# Power.net
KiCad netlist of a schematic drawn in Altium Designer
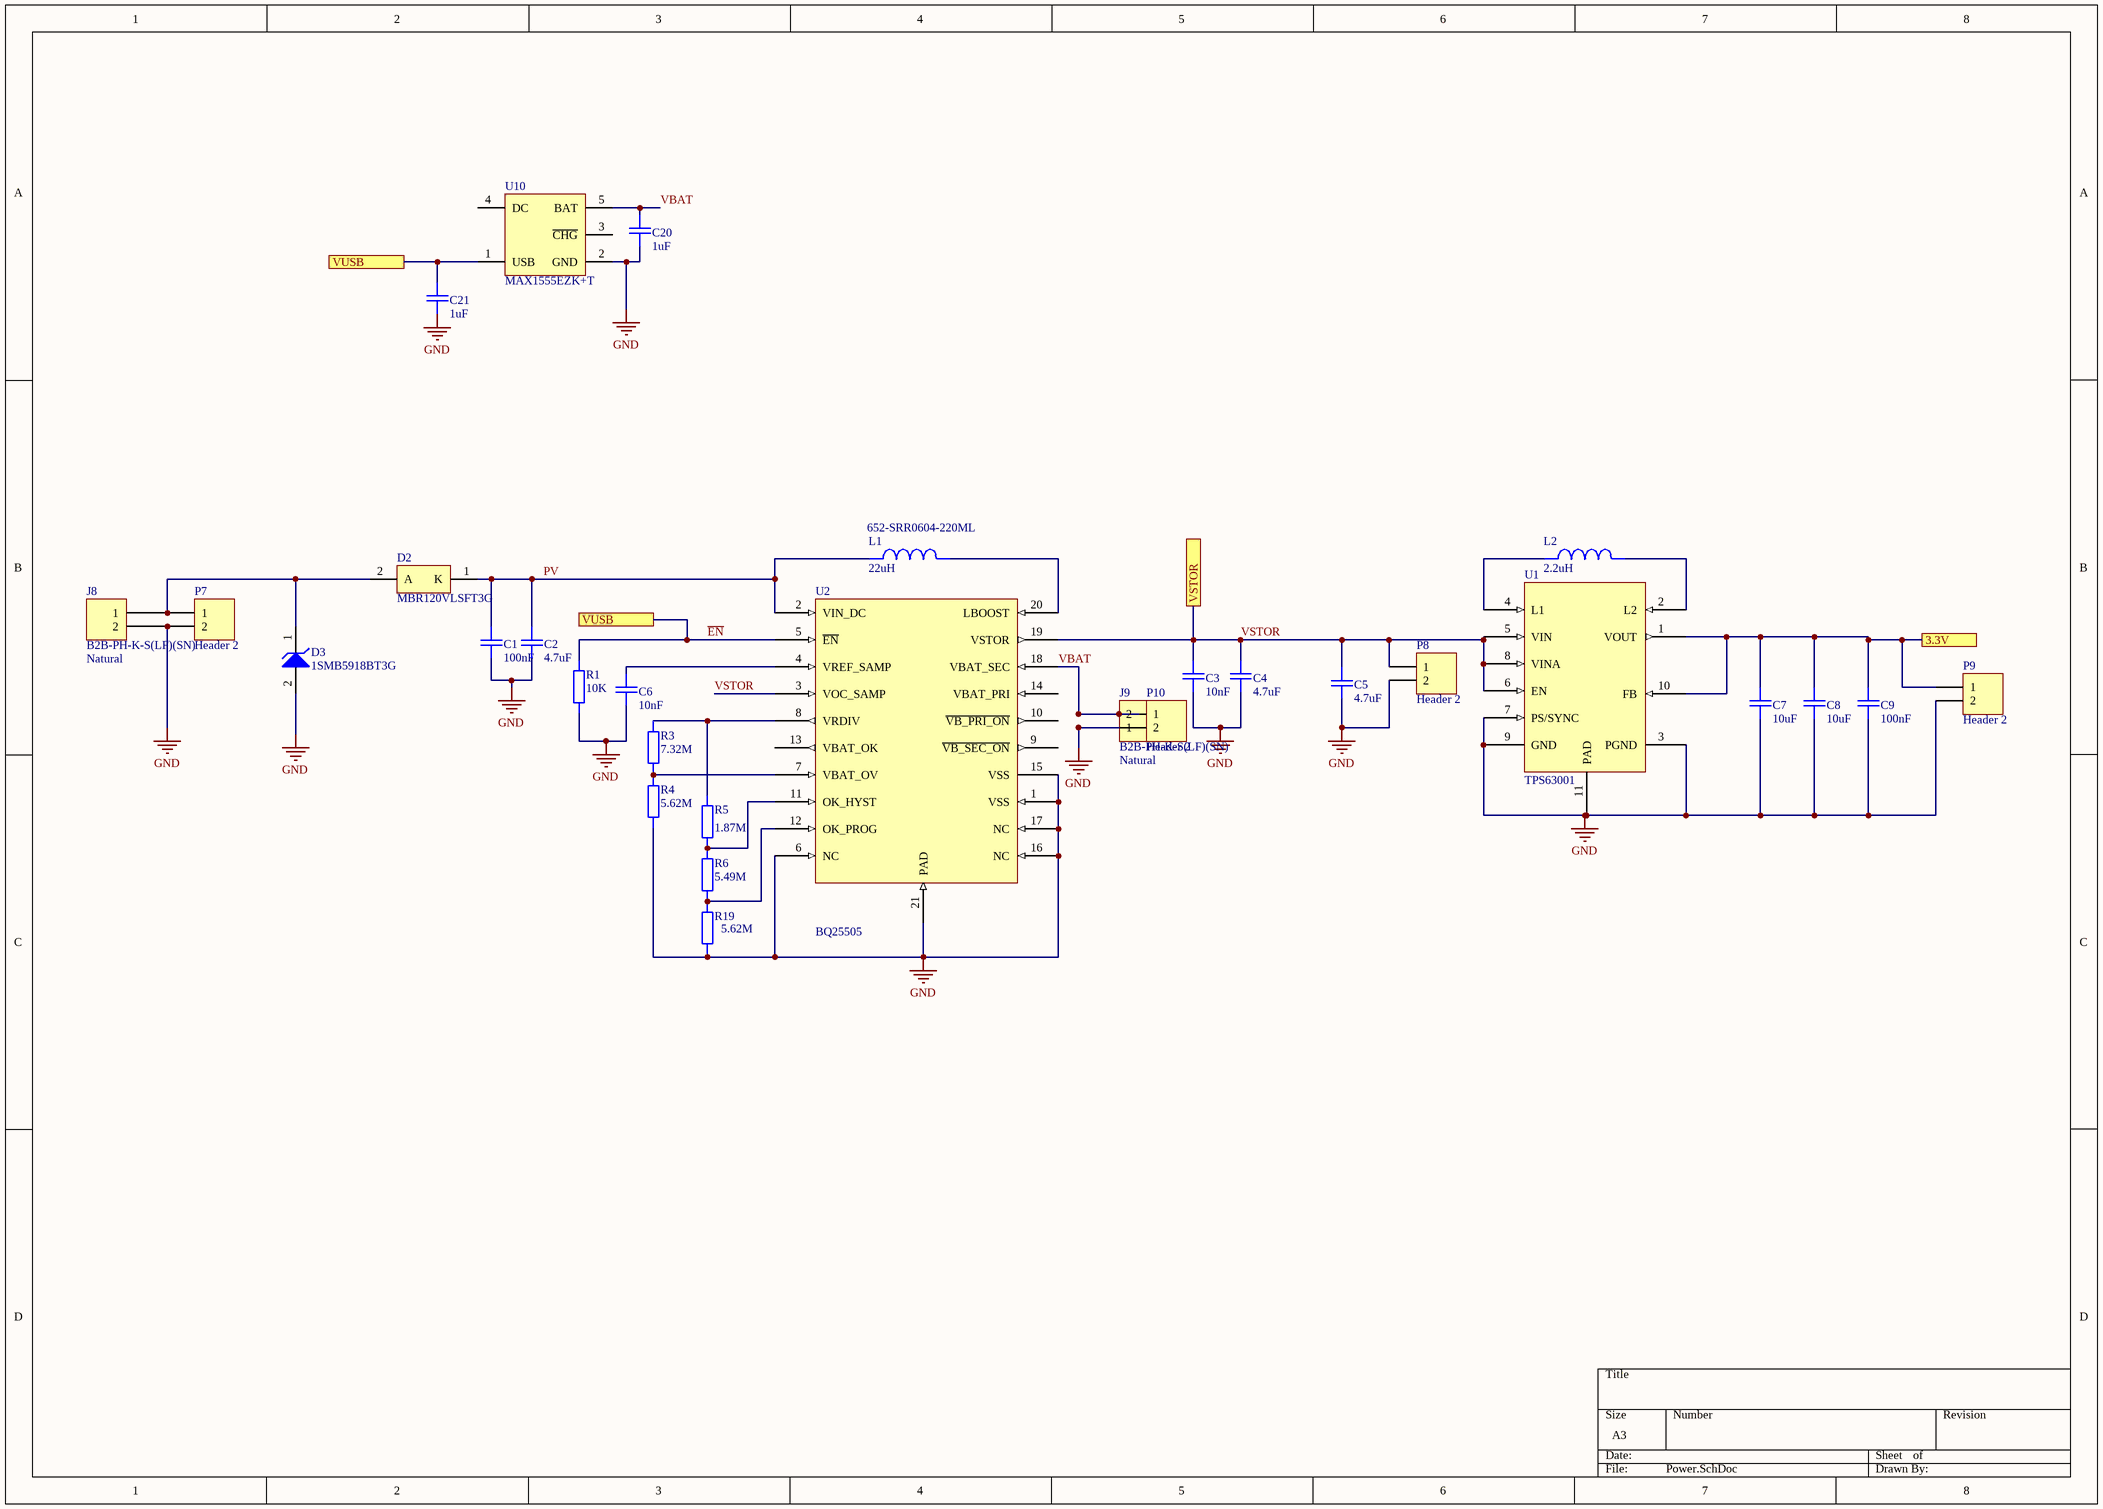
[diagram p0: Power.SchDoc]

(export (version "E")
  (design (tool "Eeschema 10.0.6"))
  (components
    (comp (ref "C1")
      (value "100nF")
      (footprint "C0805")
      (fields
        (field (name "VOLTAGE") "16V")
        (field (name "TOLERANCE") "10%")
        (field (name "Comment") "Capacitor")
      )
      (libsource (lib "Schematic Library") (part "Capacitor"))
    )
    (comp (ref "C2")
      (value "4.7uF")
      (footprint "C0805")
      (fields
        (field (name "VOLTAGE") "16V")
        (field (name "TOLERANCE") "10%")
        (field (name "Comment") "Capacitor")
      )
      (libsource (lib "Schematic Library") (part "Capacitor"))
    )
    (comp (ref "C3")
      (value "10nF")
      (footprint "C0805")
      (fields
        (field (name "VOLTAGE") "16V")
        (field (name "TOLERANCE") "10%")
        (field (name "Comment") "Capacitor")
      )
      (libsource (lib "Schematic Library") (part "Capacitor"))
    )
    (comp (ref "C4")
      (value "4.7uF")
      (footprint "C0805")
      (fields
        (field (name "VOLTAGE") "16V")
        (field (name "TOLERANCE") "10%")
        (field (name "Comment") "Capacitor")
      )
      (libsource (lib "Schematic Library") (part "Capacitor"))
    )
    (comp (ref "C5")
      (value "4.7uF")
      (footprint "C0805")
      (fields
        (field (name "VOLTAGE") "16V")
        (field (name "TOLERANCE") "10%")
        (field (name "Comment") "Capacitor")
      )
      (libsource (lib "Schematic Library") (part "Capacitor"))
    )
    (comp (ref "C6")
      (value "10nF")
      (footprint "C0805")
      (fields
        (field (name "VOLTAGE") "16V")
        (field (name "TOLERANCE") "10%")
        (field (name "Comment") "Capacitor")
      )
      (libsource (lib "Schematic Library") (part "Capacitor"))
    )
    (comp (ref "C7")
      (value "10uF")
      (footprint "C0805")
      (fields
        (field (name "VOLTAGE") "16V")
        (field (name "TOLERANCE") "10%")
        (field (name "Comment") "Capacitor")
      )
      (libsource (lib "Schematic Library") (part "Capacitor"))
    )
    (comp (ref "C8")
      (value "10uF")
      (footprint "C0805")
      (fields
        (field (name "VOLTAGE") "16V")
        (field (name "TOLERANCE") "10%")
        (field (name "Comment") "Capacitor")
      )
      (libsource (lib "Schematic Library") (part "Capacitor"))
    )
    (comp (ref "C9")
      (value "100nF")
      (footprint "C0805")
      (fields
        (field (name "VOLTAGE") "16V")
        (field (name "TOLERANCE") "10%")
        (field (name "Comment") "Capacitor")
      )
      (libsource (lib "Schematic Library") (part "Capacitor"))
    )
    (comp (ref "C20")
      (value "1uF")
      (footprint "C0805")
      (fields
        (field (name "VOLTAGE") "16V")
        (field (name "TOLERANCE") "10%")
        (field (name "Comment") "Capacitor")
      )
      (libsource (lib "Schematic Library") (part "Capacitor"))
    )
    (comp (ref "C21")
      (value "1uF")
      (footprint "C0805")
      (fields
        (field (name "VOLTAGE") "16V")
        (field (name "TOLERANCE") "10%")
        (field (name "Comment") "Capacitor")
      )
      (libsource (lib "Schematic Library") (part "Capacitor"))
    )
    (comp (ref "D2")
      (value "MBR120VLSFT3G")
      (footprint "ONSC-SOD-123FL-2-498-01_V")
      (description "Schottky Power Rectifier, 2-Pin SOD-123, Pb-Free, Tape and Reel")
      (fields (field (name "MANUFACTURER") "On Semiconductor"))
      (libsource (lib "Altium Content Vault") (part "ONSC-D-K1A2-2_A"))
    )
    (comp (ref "D3")
      (value "1SMB5918BT3G")
      (footprint "ONSC-SMB-2-403A-03_H_V")
      (description "3 W Zener Voltage Regulator, 2-Pin SMB, Pb-Free, Tape and Reel")
      (fields (field (name "MANUFACTURER") "On Semiconductor"))
      (libsource (lib "Altium Content Vault") (part "ONSC-K1A2-2"))
    )
    (comp (ref "J8")
      (value "B2B-PH-K-S(LF)(SN)")
      (footprint "JST B2B-PH-K")
      (description "CONN HEADER PH TOP 2POS 2MM")
      (fields (field (name "COLOUR") "Natural") (field (name "MANUFACTURER") "JST Sales America Inc."))
      (libsource (lib "") (part "2 Pin_1"))
    )
    (comp (ref "J9")
      (value "B2B-PH-K-S(LF)(SN)")
      (footprint "JST B2B-PH-K")
      (description "CONN HEADER PH TOP 2POS 2MM")
      (fields (field (name "COLOUR") "Natural") (field (name "MANUFACTURER") "JST Sales America Inc."))
      (libsource (lib "Celestial Library Database") (part "2 Pin"))
    )
    (comp (ref "L1")
      (value "22uH")
      (footprint "SRR0604")
      (fields
        (field (name "SUPPLIER PART NUMBER 1") "652-SRR0604-220ML")
        (field (name "MANUFACTURER") "Bourns")
        (field (name "TOLERANCE") "20%")
        (field (name "Comment") "Inductor")
      )
      (libsource (lib "Schematic Library") (part "Inductor"))
    )
    (comp (ref "L2")
      (value "2.2uH")
      (footprint "MLP2520")
      (fields (field (name "Comment") "Inductor"))
      (libsource (lib "Schematic Library") (part "Inductor"))
    )
    (comp (ref "P7")
      (value "Header 2")
      (footprint "HDR1X2")
      (description "Header, 2-Pin")
      (fields (field (name "PUBLISHER") "Altium Limited"))
      (libsource (lib "Miscellaneous Connectors") (part "Header 2"))
    )
    (comp (ref "P8")
      (value "Header 2")
      (footprint "HDR1X2")
      (description "Header, 2-Pin")
      (fields (field (name "PUBLISHER") "Altium Limited"))
      (libsource (lib "Miscellaneous Connectors") (part "Header 2"))
    )
    (comp (ref "P9")
      (value "Header 2")
      (footprint "HDR1X2")
      (description "Header, 2-Pin")
      (fields (field (name "PUBLISHER") "Altium Limited"))
      (libsource (lib "Miscellaneous Connectors") (part "Header 2"))
    )
    (comp (ref "P10")
      (value "Header 2")
      (footprint "HDR1X2")
      (description "Header, 2-Pin")
      (fields (field (name "PUBLISHER") "Altium Limited"))
      (libsource (lib "Miscellaneous Connectors") (part "Header 2"))
    )
    (comp (ref "R1")
      (value "10K")
      (footprint "6-0805_L")
      (fields (field (name "TOLERANCE") "1%") (field (name "Comment") "Resistor"))
      (libsource (lib "Schematic Library") (part "Resistor"))
    )
    (comp (ref "R3")
      (value "7.32M")
      (footprint "6-0805_L")
      (fields (field (name "TOLERANCE") "1%") (field (name "Comment") "Resistor"))
      (libsource (lib "Schematic Library") (part "Resistor"))
    )
    (comp (ref "R4")
      (value "5.62M")
      (footprint "6-0805_L")
      (fields (field (name "TOLERANCE") "1%") (field (name "Comment") "Resistor"))
      (libsource (lib "Schematic Library") (part "Resistor"))
    )
    (comp (ref "R5")
      (value "1.87M")
      (footprint "6-0805_L")
      (fields (field (name "TOLERANCE") "1%") (field (name "Comment") "Resistor"))
      (libsource (lib "Schematic Library") (part "Resistor"))
    )
    (comp (ref "R6")
      (value "5.49M")
      (footprint "6-0805_L")
      (fields (field (name "TOLERANCE") "1%") (field (name "Comment") "Resistor"))
      (libsource (lib "Schematic Library") (part "Resistor"))
    )
    (comp (ref "R19")
      (value "5.62M")
      (footprint "6-0805_L")
      (fields (field (name "TOLERANCE") "1%") (field (name "Comment") "Resistor"))
      (libsource (lib "Schematic Library") (part "Resistor"))
    )
    (comp (ref "U1")
      (value "TPS63001")
      (footprint "DRC0010J")
      (libsource (lib "Schematic Library") (part "TPS63001"))
    )
    (comp (ref "U2")
      (value "BQ25505")
      (footprint "S-PVQFN-N20")
      (libsource (lib "Schematic Library") (part "BQ25505"))
    )
    (comp (ref "U10")
      (value "MAX1555EZK+T")
      (footprint "MAXM-Z5+1_N")
      (fields (field (name "MANUFACTURER") "Maxim"))
      (libsource (lib "Altium Content Vault") (part "MAXM-MAX1555-Z5+1"))
    )
  )
  (nets
    (net (code "1") (name "/3.3V") (class "Default")
      (node (ref "C7") (pin "1") (pinfunction "1_1") (pintype "passive"))
      (node (ref "C8") (pin "1") (pinfunction "1_1") (pintype "passive"))
      (node (ref "C9") (pin "1") (pinfunction "1_1") (pintype "passive"))
      (node (ref "P9") (pin "1") (pinfunction "1_1") (pintype "passive"))
      (node (ref "U1") (pin "1") (pinfunction "VOUT_1") (pintype "output"))
      (node (ref "U1") (pin "10") (pinfunction "FB_10") (pintype "input"))
    )
    (net (code "2") (name "/PV") (class "Default")
      (node (ref "C1") (pin "1") (pinfunction "1_1") (pintype "passive"))
      (node (ref "C2") (pin "1") (pinfunction "1_1") (pintype "passive"))
      (node (ref "D2") (pin "1") (pinfunction "K_1") (pintype "passive"))
      (node (ref "L1") (pin "1") (pintype "passive"))
      (node (ref "U2") (pin "2") (pinfunction "VIN_DC_2") (pintype "input"))
    )
    (net (code "3") (name "/VBAT") (class "Default")
      (node (ref "C20") (pin "1") (pinfunction "1_1") (pintype "passive"))
      (node (ref "J9") (pin "2") (pinfunction "2_2") (pintype "passive"))
      (node (ref "P10") (pin "1") (pinfunction "1_1") (pintype "passive"))
      (node (ref "U10") (pin "5") (pinfunction "BAT_5") (pintype "power_in"))
      (node (ref "U2") (pin "18") (pinfunction "VBAT_SEC_18") (pintype "input"))
    )
    (net (code "4") (name "/VSTOR") (class "Default")
      (node (ref "C3") (pin "1") (pinfunction "1_1") (pintype "passive"))
      (node (ref "C4") (pin "1") (pinfunction "1_1") (pintype "passive"))
      (node (ref "C5") (pin "1") (pinfunction "1_1") (pintype "passive"))
      (node (ref "P8") (pin "1") (pinfunction "1_1") (pintype "passive"))
      (node (ref "U1") (pin "5") (pinfunction "VIN_5") (pintype "input"))
      (node (ref "U1") (pin "6") (pinfunction "EN_6") (pintype "input"))
      (node (ref "U1") (pin "8") (pinfunction "VINA_8") (pintype "input"))
      (node (ref "U2") (pin "19") (pinfunction "VSTOR_19") (pintype "output"))
      (node (ref "U2") (pin "3") (pinfunction "VOC_SAMP_3") (pintype "input"))
    )
    (net (code "5") (name "/~{EN}") (class "Default")
      (node (ref "C21") (pin "1") (pinfunction "1_1") (pintype "passive"))
      (node (ref "R1") (pin "1") (pinfunction "1_1") (pintype "passive"))
      (node (ref "U10") (pin "1") (pinfunction "USB_1") (pintype "power_in"))
      (node (ref "U2") (pin "5") (pinfunction "~{EN}_5") (pintype "input"))
    )
    (net (code "6") (name "GND") (class "Default")
      (node (ref "C1") (pin "2") (pinfunction "2_2") (pintype "passive"))
      (node (ref "C2") (pin "2") (pinfunction "2_2") (pintype "passive"))
      (node (ref "C20") (pin "2") (pinfunction "2_2") (pintype "passive"))
      (node (ref "C21") (pin "2") (pinfunction "2_2") (pintype "passive"))
      (node (ref "C3") (pin "2") (pinfunction "2_2") (pintype "passive"))
      (node (ref "C4") (pin "2") (pinfunction "2_2") (pintype "passive"))
      (node (ref "C5") (pin "2") (pinfunction "2_2") (pintype "passive"))
      (node (ref "C6") (pin "2") (pinfunction "2_2") (pintype "passive"))
      (node (ref "C7") (pin "2") (pinfunction "2_2") (pintype "passive"))
      (node (ref "C8") (pin "2") (pinfunction "2_2") (pintype "passive"))
      (node (ref "C9") (pin "2") (pinfunction "2_2") (pintype "passive"))
      (node (ref "D3") (pin "2") (pinfunction "A_2") (pintype "passive"))
      (node (ref "J8") (pin "2") (pinfunction "2_2") (pintype "passive"))
      (node (ref "J9") (pin "1") (pinfunction "1_1") (pintype "passive"))
      (node (ref "P10") (pin "2") (pinfunction "2_2") (pintype "passive"))
      (node (ref "P7") (pin "2") (pinfunction "2_2") (pintype "passive"))
      (node (ref "P8") (pin "2") (pinfunction "2_2") (pintype "passive"))
      (node (ref "P9") (pin "2") (pinfunction "2_2") (pintype "passive"))
      (node (ref "R1") (pin "2") (pinfunction "2_2") (pintype "passive"))
      (node (ref "R19") (pin "2") (pinfunction "2_2") (pintype "passive"))
      (node (ref "R4") (pin "2") (pinfunction "2_2") (pintype "passive"))
      (node (ref "U1") (pin "11") (pinfunction "PAD_11") (pintype "power_in"))
      (node (ref "U1") (pin "3") (pinfunction "PGND_3") (pintype "power_in"))
      (node (ref "U1") (pin "7") (pinfunction "PS/SYNC_7") (pintype "input"))
      (node (ref "U1") (pin "9") (pinfunction "GND_9") (pintype "power_in"))
      (node (ref "U10") (pin "2") (pinfunction "GND_2") (pintype "power_in"))
      (node (ref "U2") (pin "1") (pinfunction "VSS_1") (pintype "input"))
      (node (ref "U2") (pin "15") (pinfunction "VSS_15") (pintype "power_in"))
      (node (ref "U2") (pin "16") (pinfunction "NC_16") (pintype "input"))
      (node (ref "U2") (pin "17") (pinfunction "NC_17") (pintype "input"))
      (node (ref "U2") (pin "21") (pinfunction "PAD_21") (pintype "input"))
      (node (ref "U2") (pin "6") (pinfunction "NC_6") (pintype "input"))
    )
    (net (code "7") (name "Net-(D2-A)") (class "Default")
      (node (ref "D2") (pin "2") (pinfunction "A_2") (pintype "passive"))
      (node (ref "D3") (pin "1") (pinfunction "K_1") (pintype "passive"))
      (node (ref "J8") (pin "1") (pinfunction "1_1") (pintype "passive"))
      (node (ref "P7") (pin "1") (pinfunction "1_1") (pintype "passive"))
    )
    (net (code "8") (name "Net-(U1-L1)") (class "Default")
      (node (ref "L2") (pin "1") (pintype "passive"))
      (node (ref "U1") (pin "4") (pinfunction "L1_4") (pintype "input"))
    )
    (net (code "9") (name "Net-(U1-L2)") (class "Default")
      (node (ref "L2") (pin "2") (pintype "passive"))
      (node (ref "U1") (pin "2") (pinfunction "L2_2") (pintype "input"))
    )
    (net (code "10") (name "Net-(U2-LBOOST)") (class "Default")
      (node (ref "L1") (pin "2") (pintype "passive"))
      (node (ref "U2") (pin "20") (pinfunction "LBOOST_20") (pintype "input"))
    )
    (net (code "11") (name "Net-(U2-OK_HYST)") (class "Default")
      (node (ref "R5") (pin "2") (pinfunction "2_2") (pintype "passive"))
      (node (ref "R6") (pin "1") (pinfunction "1_1") (pintype "passive"))
      (node (ref "U2") (pin "11") (pinfunction "OK_HYST_11") (pintype "input"))
    )
    (net (code "12") (name "Net-(U2-OK_PROG)") (class "Default")
      (node (ref "R19") (pin "1") (pinfunction "1_1") (pintype "passive"))
      (node (ref "R6") (pin "2") (pinfunction "2_2") (pintype "passive"))
      (node (ref "U2") (pin "12") (pinfunction "OK_PROG_12") (pintype "input"))
    )
    (net (code "13") (name "Net-(U2-VBAT_OV)") (class "Default")
      (node (ref "R3") (pin "2") (pinfunction "2_2") (pintype "passive"))
      (node (ref "R4") (pin "1") (pinfunction "1_1") (pintype "passive"))
      (node (ref "U2") (pin "7") (pinfunction "VBAT_OV_7") (pintype "input"))
    )
    (net (code "14") (name "Net-(U2-VRDIV)") (class "Default")
      (node (ref "R3") (pin "1") (pinfunction "1_1") (pintype "passive"))
      (node (ref "R5") (pin "1") (pinfunction "1_1") (pintype "passive"))
      (node (ref "U2") (pin "8") (pinfunction "VRDIV_8") (pintype "output"))
    )
    (net (code "15") (name "Net-(U2-VREF_SAMP)") (class "Default")
      (node (ref "C6") (pin "1") (pinfunction "1_1") (pintype "passive"))
      (node (ref "U2") (pin "4") (pinfunction "VREF_SAMP_4") (pintype "input"))
    )
    (net (code "16") (name "unconnected-(U2-VBAT_OK-Pad13)") (class "Default")
      (node (ref "U2") (pin "13") (pinfunction "VBAT_OK_13") (pintype "output"))
    )
    (net (code "17") (name "unconnected-(U2-VBAT_PRI-Pad14)") (class "Default")
      (node (ref "U2") (pin "14") (pinfunction "VBAT_PRI_14") (pintype "input"))
    )
    (net (code "18") (name "unconnected-(U2-~{VB_PRI_ON}-Pad10)") (class "Default")
      (node (ref "U2") (pin "10") (pinfunction "~{VB_PRI_ON}_10") (pintype "output"))
    )
    (net (code "19") (name "unconnected-(U2-~{VB_SEC_ON}-Pad9)") (class "Default")
      (node (ref "U2") (pin "9") (pinfunction "~{VB_SEC_ON}_9") (pintype "output"))
    )
    (net (code "20") (name "unconnected-(U10-DC-Pad4)") (class "Default")
      (node (ref "U10") (pin "4") (pinfunction "DC_4") (pintype "power_in"))
    )
    (net (code "21") (name "unconnected-(U10-~{CHG}-Pad3)") (class "Default")
      (node (ref "U10") (pin "3") (pinfunction "~{CHG}_3") (pintype "tri_state"))
    )
  )
)
